# USBULPI.net
KiCad netlist of a schematic drawn in Altium Designer
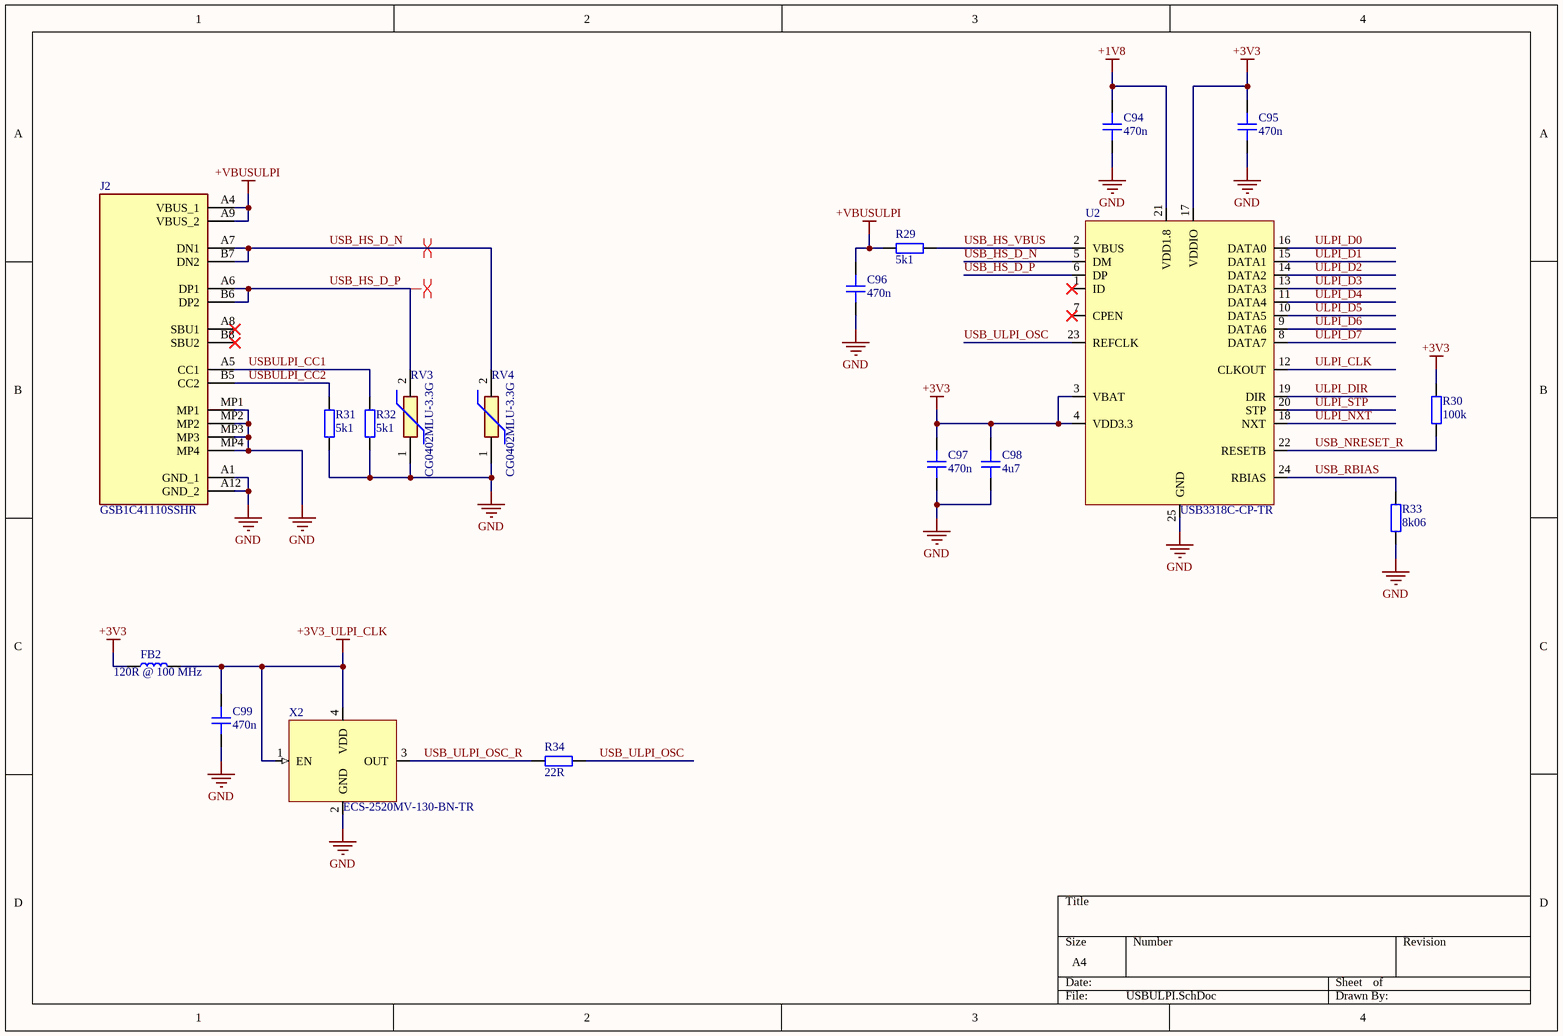
[diagram p0: USBULPI.SchDoc]

(export (version "E")
  (design (tool "Eeschema 10.0.6"))
  (components
    (comp (ref "C94")
      (value "470n")
      (footprint "CAP_0201")
      (description "Capacitor SMD 0201")
      (libsource (lib "Schematic-Lib-PhilsLab") (part "CAP_0201"))
    )
    (comp (ref "C95")
      (value "470n")
      (footprint "CAP_0201")
      (description "Capacitor SMD 0201")
      (libsource (lib "Schematic-Lib-PhilsLab") (part "CAP_0201"))
    )
    (comp (ref "C96")
      (value "470n")
      (footprint "CAP_0201")
      (description "Capacitor SMD 0201")
      (libsource (lib "Schematic-Lib-PhilsLab") (part "CAP_0201"))
    )
    (comp (ref "C97")
      (value "470n")
      (footprint "CAP_0201")
      (description "Capacitor SMD 0201")
      (libsource (lib "Schematic-Lib-PhilsLab") (part "CAP_0201"))
    )
    (comp (ref "C98")
      (value "4u7")
      (footprint "CAP_0402")
      (description "Capacitor SMD 0402")
      (libsource (lib "Schematic-Lib-PhilsLab") (part "CAP_0402"))
    )
    (comp (ref "C99")
      (value "470n")
      (footprint "CAP_0201")
      (description "Capacitor SMD 0201")
      (libsource (lib "Schematic-Lib-PhilsLab") (part "CAP_0201"))
    )
    (comp (ref "FB2")
      (value "120R @ 100 MHz")
      (footprint "Footprint-Lib-PhilsLab:IND_0201")
      (description "Inductor SMD 0201")
      (fields
        (field (name "MANUFACTURER_PART_NUMBER") "LQP03HQ56NH02D")
        (field (name "MOUSER PART NUMBER") "81-LQP03HQ56NH02D")
      )
      (libsource (lib "Schematic-Lib-PhilsLab") (part "IND_0201"))
    )
    (comp (ref "J2")
      (value "GSB1C41110SSHR")
      (footprint "Footprint-Lib-PhilsLab:GSB1C41110SSHR")
      (description "Connector")
      (libsource (lib "Schematic-Lib-PhilsLab") (part "GSB1C41110SSHR"))
    )
    (comp (ref "R29")
      (value "5k1")
      (footprint "RES_0402")
      (description "Resistor SMD 0402")
      (libsource (lib "Schematic-Lib-PhilsLab") (part "RES_0402"))
    )
    (comp (ref "R30")
      (value "100k")
      (footprint "RES_0402")
      (description "Resistor SMD 0402")
      (libsource (lib "Schematic-Lib-PhilsLab") (part "RES_0402"))
    )
    (comp (ref "R31")
      (value "5k1")
      (footprint "RES_0402")
      (description "Resistor SMD 0402")
      (libsource (lib "Schematic-Lib-PhilsLab") (part "RES_0402"))
    )
    (comp (ref "R32")
      (value "5k1")
      (footprint "RES_0402")
      (description "Resistor SMD 0402")
      (libsource (lib "Schematic-Lib-PhilsLab") (part "RES_0402"))
    )
    (comp (ref "R33")
      (value "8k06")
      (footprint "RES_0402")
      (description "Resistor SMD 0402")
      (libsource (lib "Schematic-Lib-PhilsLab") (part "RES_0402"))
    )
    (comp (ref "R34")
      (value "22R")
      (footprint "RES_0201")
      (description "Resistor SMD 0201")
      (libsource (lib "Schematic-Lib-PhilsLab") (part "RES_0201"))
    )
    (comp (ref "RV3")
      (value "CG0402MLU-3.3G")
      (footprint "Footprint-Lib-PhilsLab:VARC1005X41N")
      (description "ESD Diode")
      (fields (field (name "MOUSER PART NUMBER") "652-CG0402MLU-3.3G"))
      (libsource (lib "Schematic-Lib-PhilsLab") (part "CG0402MLU-3.3G"))
    )
    (comp (ref "RV4")
      (value "CG0402MLU-3.3G")
      (footprint "Footprint-Lib-PhilsLab:VARC1005X41N")
      (description "ESD Diode")
      (fields (field (name "MOUSER PART NUMBER") "652-CG0402MLU-3.3G"))
      (libsource (lib "Schematic-Lib-PhilsLab") (part "CG0402MLU-3.3G"))
    )
    (comp (ref "U2")
      (value "USB3318C-CP-TR")
      (footprint "QFN50P400X400X100-25N-D")
      (description "USB Interface IC High Speed USB 1.8V ULPI")
      (fields (field (name "MANUFACTURER") "Microchip"))
      (libsource (lib "Schematic-Lib-PhilsLab") (part "USB3318C-CP-TR"))
    )
    (comp (ref "X2")
      (value "ECS-2520MV-130-BN-TR")
      (footprint "XTAL_2520")
      (fields (field (name "MANUFACTURER") "ECS"))
      (libsource (lib "Schematic-Lib-PhilsLab") (part "ECS-2520MV-130-BN-TR"))
    )
  )
  (nets
    (net (code "1") (name "+1V8") (class "Default")
      (node (ref "C94") (pin "2") (pinfunction "2_2") (pintype "passive"))
      (node (ref "U2") (pin "21") (pinfunction "VDD1.8_21") (pintype "passive"))
    )
    (net (code "2") (name "+3V3") (class "Default")
      (node (ref "C95") (pin "2") (pinfunction "2_2") (pintype "passive"))
      (node (ref "C97") (pin "2") (pinfunction "2_2") (pintype "passive"))
      (node (ref "C98") (pin "2") (pinfunction "2_2") (pintype "passive"))
      (node (ref "FB2") (pin "1") (pinfunction "1_1") (pintype "passive"))
      (node (ref "R30") (pin "2") (pinfunction "2_2") (pintype "passive"))
      (node (ref "U2") (pin "17") (pinfunction "VDDIO_17") (pintype "passive"))
      (node (ref "U2") (pin "3") (pinfunction "VBAT_3") (pintype "passive"))
      (node (ref "U2") (pin "4") (pinfunction "VDD3.3_4") (pintype "passive"))
    )
    (net (code "3") (name "+3V3_ULPI_CLK") (class "Default")
      (node (ref "C99") (pin "2") (pinfunction "2_2") (pintype "passive"))
      (node (ref "FB2") (pin "2") (pinfunction "2_2") (pintype "passive"))
      (node (ref "X2") (pin "1") (pinfunction "EN_1") (pintype "input"))
      (node (ref "X2") (pin "4") (pinfunction "VDD_4") (pintype "power_in"))
    )
    (net (code "4") (name "+VBUSULPI") (class "Default")
      (node (ref "C96") (pin "2") (pinfunction "2_2") (pintype "passive"))
      (node (ref "J2") (pin "A4") (pinfunction "VBUS_1_A4") (pintype "passive"))
      (node (ref "J2") (pin "A9") (pinfunction "VBUS_2_A9") (pintype "passive"))
      (node (ref "R29") (pin "2") (pinfunction "2_2") (pintype "passive"))
    )
    (net (code "5") (name "/ULPI_CLK") (class "Default")
      (node (ref "U2") (pin "12") (pinfunction "CLKOUT_12") (pintype "passive"))
    )
    (net (code "6") (name "/ULPI_D0") (class "Default")
      (node (ref "U2") (pin "16") (pinfunction "DATA0_16") (pintype "passive"))
    )
    (net (code "7") (name "/ULPI_D1") (class "Default")
      (node (ref "U2") (pin "15") (pinfunction "DATA1_15") (pintype "passive"))
    )
    (net (code "8") (name "/ULPI_D2") (class "Default")
      (node (ref "U2") (pin "14") (pinfunction "DATA2_14") (pintype "passive"))
    )
    (net (code "9") (name "/ULPI_D3") (class "Default")
      (node (ref "U2") (pin "13") (pinfunction "DATA3_13") (pintype "passive"))
    )
    (net (code "10") (name "/ULPI_D4") (class "Default")
      (node (ref "U2") (pin "11") (pinfunction "DATA4_11") (pintype "passive"))
    )
    (net (code "11") (name "/ULPI_D5") (class "Default")
      (node (ref "U2") (pin "10") (pinfunction "DATA5_10") (pintype "passive"))
    )
    (net (code "12") (name "/ULPI_D6") (class "Default")
      (node (ref "U2") (pin "9") (pinfunction "DATA6_9") (pintype "passive"))
    )
    (net (code "13") (name "/ULPI_D7") (class "Default")
      (node (ref "U2") (pin "8") (pinfunction "DATA7_8") (pintype "passive"))
    )
    (net (code "14") (name "/ULPI_DIR") (class "Default")
      (node (ref "U2") (pin "19") (pinfunction "DIR_19") (pintype "passive"))
    )
    (net (code "15") (name "/ULPI_NXT") (class "Default")
      (node (ref "U2") (pin "18") (pinfunction "NXT_18") (pintype "passive"))
    )
    (net (code "16") (name "/ULPI_STP") (class "Default")
      (node (ref "U2") (pin "20") (pinfunction "STP_20") (pintype "passive"))
    )
    (net (code "17") (name "/USBULPI_CC1") (class "Default")
      (node (ref "J2") (pin "A5") (pinfunction "CC1_A5") (pintype "passive"))
      (node (ref "R32") (pin "2") (pinfunction "2_2") (pintype "passive"))
    )
    (net (code "18") (name "/USBULPI_CC2") (class "Default")
      (node (ref "J2") (pin "B5") (pinfunction "CC2_B5") (pintype "passive"))
      (node (ref "R31") (pin "2") (pinfunction "2_2") (pintype "passive"))
    )
    (net (code "19") (name "/USB_HS_D_N") (class "Default")
      (node (ref "J2") (pin "A7") (pinfunction "DN1_A7") (pintype "passive"))
      (node (ref "J2") (pin "B7") (pinfunction "DN2_B7") (pintype "passive"))
      (node (ref "RV4") (pin "2") (pinfunction "2_2") (pintype "passive"))
      (node (ref "U2") (pin "5") (pinfunction "DM_5") (pintype "passive"))
    )
    (net (code "20") (name "/USB_HS_D_P") (class "Default")
      (node (ref "J2") (pin "A6") (pinfunction "DP1_A6") (pintype "passive"))
      (node (ref "J2") (pin "B6") (pinfunction "DP2_B6") (pintype "passive"))
      (node (ref "RV3") (pin "2") (pinfunction "2_2") (pintype "passive"))
      (node (ref "U2") (pin "6") (pinfunction "DP_6") (pintype "passive"))
    )
    (net (code "21") (name "/USB_HS_VBUS") (class "Default")
      (node (ref "R29") (pin "1") (pinfunction "1_1") (pintype "passive"))
      (node (ref "U2") (pin "2") (pinfunction "VBUS_2") (pintype "passive"))
    )
    (net (code "22") (name "/USB_NRESET_R") (class "Default")
      (node (ref "R30") (pin "1") (pinfunction "1_1") (pintype "passive"))
      (node (ref "U2") (pin "22") (pinfunction "RESETB_22") (pintype "passive"))
    )
    (net (code "23") (name "/USB_RBIAS") (class "Default")
      (node (ref "R33") (pin "2") (pinfunction "2_2") (pintype "passive"))
      (node (ref "U2") (pin "24") (pinfunction "RBIAS_24") (pintype "passive"))
    )
    (net (code "24") (name "/USB_ULPI_OSC") (class "Default")
      (node (ref "R34") (pin "2") (pinfunction "2_2") (pintype "passive"))
      (node (ref "U2") (pin "23") (pinfunction "REFCLK_23") (pintype "passive"))
    )
    (net (code "25") (name "/USB_ULPI_OSC_R") (class "Default")
      (node (ref "R34") (pin "1") (pinfunction "1_1") (pintype "passive"))
      (node (ref "X2") (pin "3") (pinfunction "OUT_3") (pintype "passive"))
    )
    (net (code "26") (name "GND") (class "Default")
      (node (ref "C94") (pin "1") (pinfunction "1_1") (pintype "passive"))
      (node (ref "C95") (pin "1") (pinfunction "1_1") (pintype "passive"))
      (node (ref "C96") (pin "1") (pinfunction "1_1") (pintype "passive"))
      (node (ref "C97") (pin "1") (pinfunction "1_1") (pintype "passive"))
      (node (ref "C98") (pin "1") (pinfunction "1_1") (pintype "passive"))
      (node (ref "C99") (pin "1") (pinfunction "1_1") (pintype "passive"))
      (node (ref "J2") (pin "A1") (pinfunction "GND_1_A1") (pintype "passive"))
      (node (ref "J2") (pin "A12") (pinfunction "GND_2_A12") (pintype "passive"))
      (node (ref "J2") (pin "MP1") (pinfunction "MP1_MP1") (pintype "passive"))
      (node (ref "J2") (pin "MP2") (pinfunction "MP2_MP2") (pintype "passive"))
      (node (ref "J2") (pin "MP3") (pinfunction "MP3_MP3") (pintype "passive"))
      (node (ref "J2") (pin "MP4") (pinfunction "MP4_MP4") (pintype "passive"))
      (node (ref "R31") (pin "1") (pinfunction "1_1") (pintype "passive"))
      (node (ref "R32") (pin "1") (pinfunction "1_1") (pintype "passive"))
      (node (ref "R33") (pin "1") (pinfunction "1_1") (pintype "passive"))
      (node (ref "RV3") (pin "1") (pinfunction "1_1") (pintype "passive"))
      (node (ref "RV4") (pin "1") (pinfunction "1_1") (pintype "passive"))
      (node (ref "U2") (pin "25") (pinfunction "GND_25") (pintype "passive"))
      (node (ref "X2") (pin "2") (pinfunction "GND_2") (pintype "power_in"))
    )
    (net (code "27") (name "unconnected-(J2-SBU1-PadA8)") (class "Default")
      (node (ref "J2") (pin "A8") (pinfunction "SBU1_A8") (pintype "passive+no_connect"))
    )
    (net (code "28") (name "unconnected-(J2-SBU2-PadB8)") (class "Default")
      (node (ref "J2") (pin "B8") (pinfunction "SBU2_B8") (pintype "passive+no_connect"))
    )
    (net (code "29") (name "unconnected-(U2-CPEN-Pad7)") (class "Default")
      (node (ref "U2") (pin "7") (pinfunction "CPEN_7") (pintype "passive+no_connect"))
    )
    (net (code "30") (name "unconnected-(U2-ID-Pad1)") (class "Default")
      (node (ref "U2") (pin "1") (pinfunction "ID_1") (pintype "passive+no_connect"))
    )
  )
)
